# ProtectedLDO.net
KiCad netlist of a schematic drawn in Altium Designer
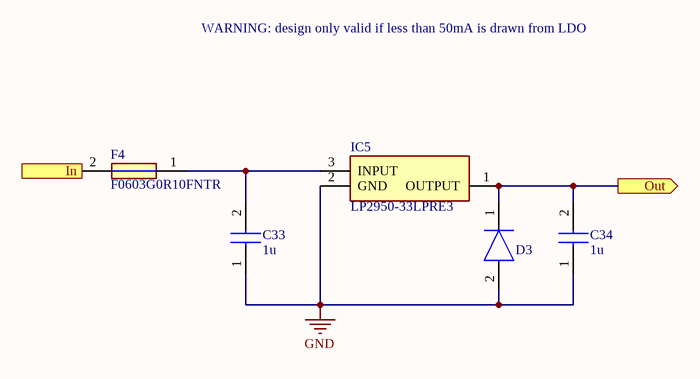
[diagram p0: ProtectedLDO.SchDoc]

(export (version "E")
  (design (tool "Eeschema 10.0.6"))
  (components
    (comp (ref "C33")
      (value "1u")
      (footprint "SamacSys:CAPC1608X90N")
      (description "Capacitor")
      (fields
        (field (name "MANUFACTURER_PART_NUMBER") "C0603C105K9PACTU")
        (field (name "MOUSER PART NUMBER") "80-C0603C105K9P")
      )
      (libsource (lib "*") (part "C0603C105K9PACTU"))
    )
    (comp (ref "C34")
      (value "1u")
      (footprint "SamacSys:CAPC1608X90N")
      (description "Capacitor")
      (fields
        (field (name "MANUFACTURER_PART_NUMBER") "C0603C105K9PACTU")
        (field (name "MOUSER PART NUMBER") "80-C0603C105K9P")
      )
      (libsource (lib "*") (part "C0603C105K9PACTU"))
    )
    (comp (ref "D3")
      (value "BZY55B3V3_RBG")
      (footprint "SamacSys:BZY55B3V3RBG")
      (description "Diode")
      (fields
        (field (name "MANUFACTURER_PART_NUMBER") "BZY55B3V3 RBG")
        (field (name "MOUSER PART NUMBER") "821-BZY55B3V3RBG")
      )
      (libsource (lib "*") (part "BZY55B3V3_RBG"))
    )
    (comp (ref "F4")
      (value "F0603G0R10FNTR")
      (footprint "SamacSys:F0603G0R10FNTR")
      (description "Fuse")
      (fields (field (name "MOUSER PART NUMBER") "581-F0603G0R10FNTR"))
      (libsource (lib "*") (part "F0603G0R10FNTR"))
    )
    (comp (ref "IC5")
      (value "LP2950-33LPRE3")
      (footprint "SamacSys:TL431CLP")
      (description "Integrated Circuit")
      (fields (field (name "MOUSER PART NUMBER") "595-LP2950-33LPRE3"))
      (libsource (lib "*") (part "LP2950-33LPRE3"))
    )
  )
  (nets
    (net (code "1") (name "/In") (class "Default")
      (node (ref "F4") (pin "2") (pinfunction "2_2") (pintype "passive"))
    )
    (net (code "2") (name "/Out") (class "Default")
      (node (ref "C34") (pin "2") (pinfunction "2_2") (pintype "passive"))
      (node (ref "D3") (pin "1") (pinfunction "K_1") (pintype "passive"))
      (node (ref "IC5") (pin "1") (pinfunction "OUTPUT_1") (pintype "passive"))
    )
    (net (code "3") (name "GND") (class "Default")
      (node (ref "C33") (pin "1") (pinfunction "1_1") (pintype "passive"))
      (node (ref "C34") (pin "1") (pinfunction "1_1") (pintype "passive"))
      (node (ref "D3") (pin "2") (pinfunction "A_2") (pintype "passive"))
      (node (ref "IC5") (pin "2") (pinfunction "GND_2") (pintype "passive"))
    )
    (net (code "4") (name "Net-(IC5-INPUT)") (class "Default")
      (node (ref "C33") (pin "2") (pinfunction "2_2") (pintype "passive"))
      (node (ref "F4") (pin "1") (pinfunction "1_1") (pintype "passive"))
      (node (ref "IC5") (pin "3") (pinfunction "INPUT_3") (pintype "passive"))
    )
  )
)
